# Flight_Controller_SCH.net
KiCad netlist of a schematic drawn in Altium Designer
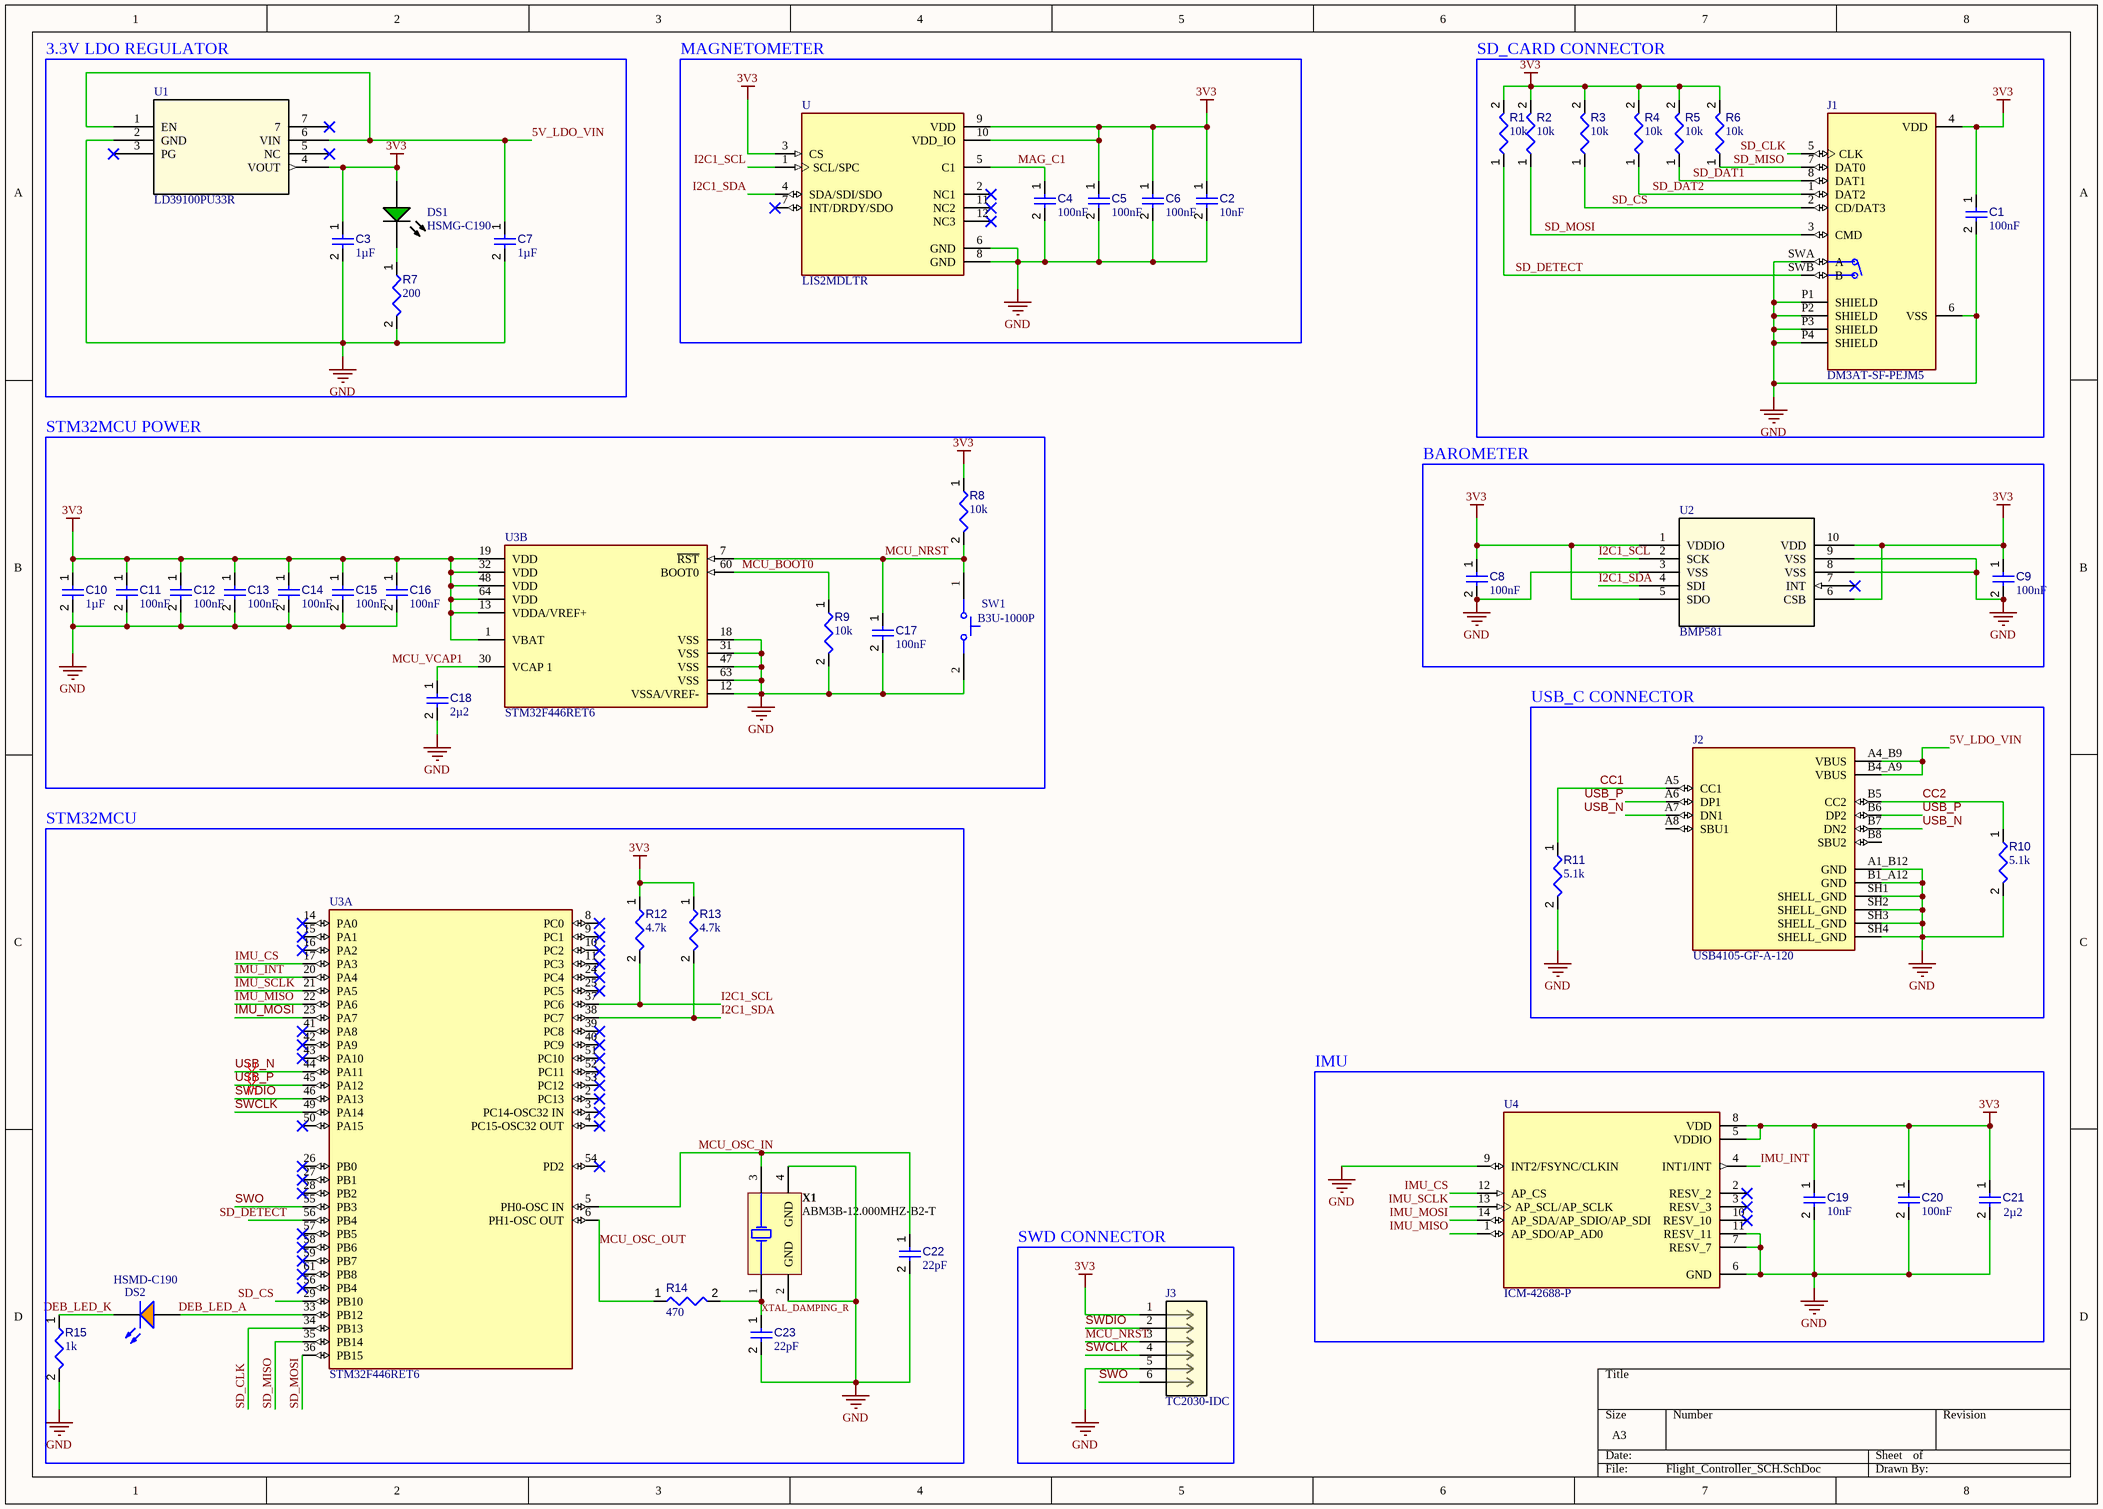
[diagram p0: Flight_Controller_SCH.SchDoc]

(export (version "E")
  (design (tool "Eeschema 10.0.6"))
  (components
    (comp (ref "C1")
      (value "100nF")
      (footprint "CAPC0402(1005)60_L")
      (description "Chip Capacitor, 100nF +/-20%, 25V, 0402, Thickness 0.6 mm")
      (fields (field (name "TOLERANCE") "10%") (field (name "Comment") "Capacitor 100nF +/-20% 25V 0402"))
      (libsource (lib "Jstephe001 Jstephe001") (part "CAP-NP-2"))
    )
    (comp (ref "C2")
      (value "10nF")
      (footprint "CAPC0402(1005)60_L")
      (description "Chip Capacitor, 10nF +/-20%, 50V, 0402, Thickness 0.6 mm")
      (fields (field (name "TOLERANCE") "5%") (field (name "Comment") "Capacitor 10nF +/-20% 50V 0402"))
      (libsource (lib "Jstephe001 Jstephe001") (part "CAP-NP-2"))
    )
    (comp (ref "C3")
      (value "1µF")
      (footprint "CAPC1608X90X35ML15T15")
      (description "Chip Capacitor, 1 uF, +/- 10%, 16 V, 0603 (1608 Metric)")
      (fields (field (name "TOLERANCE") "10%") (field (name "Comment") "Capacitor 1uF +/- 10% 16V 0603"))
      (libsource (lib "Jstephe001 Jstephe001") (part "CAP-NP-2"))
    )
    (comp (ref "C4")
      (value "100nF")
      (footprint "CAPC0402(1005)60_L")
      (description "Chip Capacitor, 100nF +/-20%, 25V, 0402, Thickness 0.6 mm")
      (fields (field (name "TOLERANCE") "10%") (field (name "Comment") "Capacitor 100nF +/-20% 25V 0402"))
      (libsource (lib "Jstephe001 Jstephe001") (part "CAP-NP-2"))
    )
    (comp (ref "C5")
      (value "100nF")
      (footprint "CAPC0402(1005)60_L")
      (description "Chip Capacitor, 100nF +/-20%, 25V, 0402, Thickness 0.6 mm")
      (fields (field (name "TOLERANCE") "10%") (field (name "Comment") "Capacitor 100nF +/-20% 25V 0402"))
      (libsource (lib "Jstephe001 Jstephe001") (part "CAP-NP-2"))
    )
    (comp (ref "C6")
      (value "100nF")
      (footprint "CAPC0402(1005)60_L")
      (description "Chip Capacitor, 100nF +/-20%, 25V, 0402, Thickness 0.6 mm")
      (fields (field (name "TOLERANCE") "10%") (field (name "Comment") "Capacitor 100nF +/-20% 25V 0402"))
      (libsource (lib "Jstephe001 Jstephe001") (part "CAP-NP-2"))
    )
    (comp (ref "C7")
      (value "1µF")
      (footprint "CAPC1608X90X35ML15T15")
      (description "Chip Capacitor, 1 uF, +/- 10%, 16 V, 0603 (1608 Metric)")
      (fields (field (name "TOLERANCE") "10%") (field (name "Comment") "Capacitor 1uF +/- 10% 16V 0603"))
      (libsource (lib "Jstephe001 Jstephe001") (part "CAP-NP-2"))
    )
    (comp (ref "C8")
      (value "100nF")
      (footprint "CAPC0402(1005)60_L")
      (description "Chip Capacitor, 100nF +/-20%, 25V, 0402, Thickness 0.6 mm")
      (fields (field (name "TOLERANCE") "10%") (field (name "Comment") "Capacitor 100nF +/-20% 25V 0402"))
      (libsource (lib "Jstephe001 Jstephe001") (part "CAP-NP-2"))
    )
    (comp (ref "C9")
      (value "100nF")
      (footprint "CAPC0402(1005)60_L")
      (description "Chip Capacitor, 100nF +/-20%, 25V, 0402, Thickness 0.6 mm")
      (fields (field (name "TOLERANCE") "10%") (field (name "Comment") "Capacitor 100nF +/-20% 25V 0402"))
      (libsource (lib "Jstephe001 Jstephe001") (part "CAP-NP-2"))
    )
    (comp (ref "C10")
      (value "1µF")
      (footprint "CAPC1608X90X35ML15T15")
      (description "Chip Capacitor, 1 uF, +/- 10%, 16 V, 0603 (1608 Metric)")
      (fields (field (name "TOLERANCE") "10%") (field (name "Comment") "Capacitor 1uF +/- 10% 16V 0603"))
      (libsource (lib "Jstephe001 Jstephe001") (part "CAP-NP-2"))
    )
    (comp (ref "C11")
      (value "100nF")
      (footprint "CAPC0402(1005)60_L")
      (description "Chip Capacitor, 100nF +/-20%, 25V, 0402, Thickness 0.6 mm")
      (fields (field (name "TOLERANCE") "10%") (field (name "Comment") "Capacitor 100nF +/-20% 25V 0402"))
      (libsource (lib "Jstephe001 Jstephe001") (part "CAP-NP-2"))
    )
    (comp (ref "C12")
      (value "100nF")
      (footprint "CAPC0402(1005)60_L")
      (description "Chip Capacitor, 100nF +/-20%, 25V, 0402, Thickness 0.6 mm")
      (fields (field (name "TOLERANCE") "10%") (field (name "Comment") "Capacitor 100nF +/-20% 25V 0402"))
      (libsource (lib "Jstephe001 Jstephe001") (part "CAP-NP-2"))
    )
    (comp (ref "C13")
      (value "100nF")
      (footprint "CAPC0402(1005)60_L")
      (description "Chip Capacitor, 100nF +/-20%, 25V, 0402, Thickness 0.6 mm")
      (fields (field (name "TOLERANCE") "10%") (field (name "Comment") "Capacitor 100nF +/-20% 25V 0402"))
      (libsource (lib "Jstephe001 Jstephe001") (part "CAP-NP-2"))
    )
    (comp (ref "C14")
      (value "100nF")
      (footprint "CAPC0402(1005)60_L")
      (description "Chip Capacitor, 100nF +/-20%, 25V, 0402, Thickness 0.6 mm")
      (fields (field (name "TOLERANCE") "10%") (field (name "Comment") "Capacitor 100nF +/-20% 25V 0402"))
      (libsource (lib "Jstephe001 Jstephe001") (part "CAP-NP-2"))
    )
    (comp (ref "C15")
      (value "100nF")
      (footprint "CAPC0402(1005)60_L")
      (description "Chip Capacitor, 100nF +/-20%, 25V, 0402, Thickness 0.6 mm")
      (fields (field (name "TOLERANCE") "10%") (field (name "Comment") "Capacitor 100nF +/-20% 25V 0402"))
      (libsource (lib "Jstephe001 Jstephe001") (part "CAP-NP-2"))
    )
    (comp (ref "C16")
      (value "100nF")
      (footprint "CAPC0402(1005)60_L")
      (description "Chip Capacitor, 100nF +/-20%, 25V, 0402, Thickness 0.6 mm")
      (fields (field (name "TOLERANCE") "10%") (field (name "Comment") "Capacitor 100nF +/-20% 25V 0402"))
      (libsource (lib "Jstephe001 Jstephe001") (part "CAP-NP-2"))
    )
    (comp (ref "C17")
      (value "100nF")
      (footprint "CAPC0402(1005)60_L")
      (description "Chip Capacitor, 100nF +/-20%, 25V, 0402, Thickness 0.6 mm")
      (fields (field (name "TOLERANCE") "10%") (field (name "Comment") "Capacitor 100nF +/-20% 25V 0402"))
      (libsource (lib "Jstephe001 Jstephe001") (part "CAP-NP-2"))
    )
    (comp (ref "C18")
      (value "2µ2")
      (footprint "CAPC0402(1005)60_L")
      (description "Chip Capacitor, 2,2µF +/-20%, 10V, 0402, Thickness 0.6 mm")
      (fields (field (name "TOLERANCE") "10%") (field (name "Comment") "Capacitor 2,2µF +/-20% 10V 0402"))
      (libsource (lib "Jstephe001 Jstephe001") (part "CAP-NP-2"))
    )
    (comp (ref "C19")
      (value "10nF")
      (footprint "CAPC0402(1005)60_L")
      (description "Chip Capacitor, 10nF +/-20%, 50V, 0402, Thickness 0.6 mm")
      (fields (field (name "TOLERANCE") "5%") (field (name "Comment") "Capacitor 10nF +/-20% 50V 0402"))
      (libsource (lib "Jstephe001 Jstephe001") (part "CAP-NP-2"))
    )
    (comp (ref "C20")
      (value "100nF")
      (footprint "CAPC1005X56X25LL10T15")
      (description "Chip Capacitor, 0.1 uF, +/- 5%, 16 V, 0402 (1005 Metric)")
      (fields (field (name "TOLERANCE") "5%") (field (name "Comment") "Capacitor 0.1 uF +/- 5% 16 V 0402"))
      (libsource (lib "Jstephe001 Jstephe001") (part "CAP-NP-2"))
    )
    (comp (ref "C21")
      (value "2µ2")
      (footprint "CAPC0402(1005)60_L")
      (description "Chip Capacitor, 2,2µF +/-20%, 10V, 0402, Thickness 0.6 mm")
      (fields (field (name "TOLERANCE") "10%") (field (name "Comment") "Capacitor 2,2µF +/-20% 10V 0402"))
      (libsource (lib "Jstephe001 Jstephe001") (part "CAP-NP-2"))
    )
    (comp (ref "C22")
      (value "22pF")
      (footprint "CAPC0402(1005)60_L")
      (description "Chip Capacitor, 22pF +/-10%, 50V, 0402, Thickness 0.6 mm")
      (fields (field (name "TOLERANCE") "10%") (field (name "Comment") "Capacitor 22pF +/-10% 50V 0402"))
      (libsource (lib "Jstephe001 Jstephe001") (part "CAP-NP-2"))
    )
    (comp (ref "C23")
      (value "22pF")
      (footprint "CAPC0402(1005)60_L")
      (description "Chip Capacitor, 22pF +/-10%, 50V, 0402, Thickness 0.6 mm")
      (fields (field (name "TOLERANCE") "10%") (field (name "Comment") "Capacitor 22pF +/-10% 50V 0402"))
      (libsource (lib "Jstephe001 Jstephe001") (part "CAP-NP-2"))
    )
    (comp (ref "DS1")
      (value "HSMG-C190")
      (footprint "AVAG-HSMX-C190_V")
      (description "LED Uni-Color Green, 52 mW, 20 mA, -40 to 85 degC, 2-Pin SMD, RoHS, Tape and Reel")
      (fields (field (name "POWER") "52mW") (field (name "MANUFACTURER") "Avago"))
      (libsource (lib "Jstephe001 Jstephe001") (part "LED-GREEN-AK-2"))
    )
    (comp (ref "DS2")
      (value "HSMD-C190")
      (footprint "AVAG-HSMX-C190_V")
      (description "LED Uni-Color Orange, 52 mW, 20 mA, -40 to 85 degC, 2-Pin SMD, RoHS, Tape and Reel")
      (fields (field (name "MANUFACTURER") "Avago") (field (name "POWER") "52mW"))
      (libsource (lib "Jstephe001 Jstephe001") (part "LED-ORANGE-AK-2"))
    )
    (comp (ref "J1")
      (value "DM3AT-SF-PEJM5")
      (footprint "HRS_DM3AT-SF-PEJM5")
      (description "10 (8 + 2) Position Card Connector Secure Digital - microSDâ„¢ Surface Mount, Right Angle Gold")
      (fields (field (name "MANUFACTURER") "Hirose Electric Co Ltd"))
      (libsource (lib "Flight_ControllerLib") (part "DM3AT-SF-PEJM5"))
    )
    (comp (ref "J2")
      (value "USB4105-GF-A-120")
      (footprint "GCT_USB4105-GF-A-120")
      (fields (field (name "MF") "Global Connector Technology"))
      (libsource (lib "Jstephe001 Jstephe001") (part "USB4105-GF-A-120"))
    )
    (comp (ref "J3")
      (value "TC2030-IDC")
      (footprint "CONN_TC2030-IDC_TGC")
      (description "Description")
      (libsource (lib "Flight_ControllerLib") (part "TC2030-IDC"))
    )
    (comp (ref "R1")
      (value "10k")
      (footprint "RESC0402(1005)_L")
      (description "Chip Resistor, 10 kOhms, +/-1 %, 63 mW, -55 to 125 degC, 0402")
      (fields (field (name "POWER") "63mW") (field (name "TOLERANCE") "1%"))
      (libsource (lib "Jstephe001 Jstephe001") (part "RES-2"))
    )
    (comp (ref "R2")
      (value "10k")
      (footprint "RESC0402(1005)_L")
      (description "Chip Resistor, 10 kOhms, +/-1 %, 63 mW, -55 to 125 degC, 0402")
      (fields (field (name "POWER") "63mW") (field (name "TOLERANCE") "1%"))
      (libsource (lib "Jstephe001 Jstephe001") (part "RES-2"))
    )
    (comp (ref "R3")
      (value "10k")
      (footprint "RESC0402(1005)_L")
      (description "Chip Resistor, 10 kOhms, +/-1 %, 63 mW, -55 to 125 degC, 0402")
      (fields (field (name "POWER") "63mW") (field (name "TOLERANCE") "1%"))
      (libsource (lib "Jstephe001 Jstephe001") (part "RES-2"))
    )
    (comp (ref "R4")
      (value "10k")
      (footprint "RESC0402(1005)_L")
      (description "Chip Resistor, 10 kOhms, +/-1 %, 63 mW, -55 to 125 degC, 0402")
      (fields (field (name "POWER") "63mW") (field (name "TOLERANCE") "1%"))
      (libsource (lib "Jstephe001 Jstephe001") (part "RES-2"))
    )
    (comp (ref "R5")
      (value "10k")
      (footprint "RESC0402(1005)_L")
      (description "Chip Resistor, 10 kOhms, +/-1 %, 63 mW, -55 to 125 degC, 0402")
      (fields (field (name "POWER") "63mW") (field (name "TOLERANCE") "1%"))
      (libsource (lib "Jstephe001 Jstephe001") (part "RES-2"))
    )
    (comp (ref "R6")
      (value "10k")
      (footprint "RESC0402(1005)_L")
      (description "Chip Resistor, 10 kOhms, +/-1 %, 63 mW, -55 to 125 degC, 0402")
      (fields (field (name "POWER") "63mW") (field (name "TOLERANCE") "1%"))
      (libsource (lib "Jstephe001 Jstephe001") (part "RES-2"))
    )
    (comp (ref "R7")
      (value "200")
      (footprint "RESC0402(1005)_L")
      (description "Chip Resistor, 10 kOhms, +/-1 %, 63 mW, -55 to 125 degC, 0402")
      (fields (field (name "POWER") "63mW") (field (name "TOLERANCE") "1%"))
      (libsource (lib "Jstephe001 Jstephe001") (part "RES-2"))
    )
    (comp (ref "R8")
      (value "10k")
      (footprint "RESC0402(1005)_L")
      (description "Chip Resistor, 10 kOhms, +/-1 %, 63 mW, -55 to 125 degC, 0402")
      (fields (field (name "POWER") "63mW") (field (name "TOLERANCE") "1%"))
      (libsource (lib "Jstephe001 Jstephe001") (part "RES-2"))
    )
    (comp (ref "R9")
      (value "10k")
      (footprint "RESC0402(1005)_L")
      (description "Chip Resistor, 10 kOhms, +/-1 %, 63 mW, -55 to 125 degC, 0402")
      (fields (field (name "POWER") "63mW") (field (name "TOLERANCE") "1%"))
      (libsource (lib "Jstephe001 Jstephe001") (part "RES-2"))
    )
    (comp (ref "R10")
      (value "5.1k")
      (footprint "RESC1005X40N")
      (description "Res Thick Film 0402 5.1K Ohm 1% 0.063W(1/16W) ±100ppm/C Pad SMD T/R")
      (fields (field (name "TOLERANCE") "1%") (field (name "Comment") "0402WGF5101TCE"))
      (libsource (lib "Jstephe001 Jstephe001") (part "RES-2"))
    )
    (comp (ref "R11")
      (value "5.1k")
      (footprint "RESC1005X40N")
      (description "Res Thick Film 0402 5.1K Ohm 1% 0.063W(1/16W) ±100ppm/C Pad SMD T/R")
      (fields (field (name "TOLERANCE") "1%") (field (name "Comment") "0402WGF5101TCE"))
      (libsource (lib "Jstephe001 Jstephe001") (part "RES-2"))
    )
    (comp (ref "R12")
      (value "4.7k")
      (footprint "RESC1005X40X25ML05T05")
      (description "Chip Resistor, 4.7 KOhm, +/- 1%, 0.1 W, -55 to 155 degC, 0402 (1005 Metric)")
      (fields (field (name "POWER") "100mW") (field (name "TOLERANCE") "1%"))
      (libsource (lib "Jstephe001 Jstephe001") (part "RES-2"))
    )
    (comp (ref "R13")
      (value "4.7k")
      (footprint "RESC1005X40X25ML05T05")
      (description "Chip Resistor, 4.7 KOhm, +/- 1%, 0.1 W, -55 to 155 degC, 0402 (1005 Metric)")
      (fields (field (name "POWER") "100mW") (field (name "TOLERANCE") "1%"))
      (libsource (lib "Jstephe001 Jstephe001") (part "RES-2"))
    )
    (comp (ref "R14")
      (value "470")
      (footprint "RESC0805(2012)_L")
      (description "Chip Resistor, 470 Ohms, +/-5%, 125 mW, -55 to 155 degC, 0805")
      (fields (field (name "TOLERANCE") "5%") (field (name "POWER") "125mW"))
      (libsource (lib "Jstephe001 Jstephe001") (part "RES-2"))
    )
    (comp (ref "R15")
      (value "1k")
      (footprint "RESC0402(1005)_L")
      (description "Chip Resistor, 1 kOhms, +/-5 %, 63 mW, -55 to 155 degC, 0402")
      (fields (field (name "TOLERANCE") "5%") (field (name "POWER") "63mW"))
      (libsource (lib "Jstephe001 Jstephe001") (part "RES-2"))
    )
    (comp (ref "SW1")
      (value "B3U-1000P")
      (footprint "OMRON-B3U-1000_V")
      (description "Tactile Switch, SPST-NO, 0.05 A, 12 V, -25 to 70 degC, 2-Pin SMD, RoHS, Tape and Reel")
      (fields (field (name "MANUFACTURER") "Omron Electronic Components"))
      (libsource (lib "Jstephe001 Jstephe001") (part "SW-SPST-NO-2"))
    )
    (comp (ref "U")
      (value "LIS2MDLTR")
      (footprint "LIS2MDLTR")
      (description "Magnetoresistive Sensor X, Y, Z Axis 12-LGA _2x2_")
      (fields (field (name "MANUFACTURER") "STMicroelectronics"))
      (libsource (lib "Flight_ControllerLib") (part "LIS2MDLTR"))
    )
    (comp (ref "U1")
      (value "LD39100PU33R")
      (footprint "DFN_00PU33R_STM")
      (description "1 A low quiescent current low noise voltage regulator")
      (libsource (lib "Flight_ControllerLib") (part "LD39100PU33R"))
    )
    (comp (ref "U2")
      (value "BMP581")
      (footprint "QFN10_BMP581_BOS-M")
      (description "No Description Available")
      (fields (field (name "COPYRIGHT") "Copyright (C) 2026 Ultra Librarian. All rights reserved."))
      (libsource (lib "Flight_ControllerLib") (part "BMP581"))
    )
    (comp (ref "U3")
      (value "STM32F446RET6")
      (footprint "FP-LQFP64-5W-MFG")
      (description "IC MCU 32BIT 512KB FLASH 64LQFP")
      (fields
        (field (name "OCTOPART") "https://octopart.com/stm32f446ret6-stmicroelectronics-52642920")
        (field (name "MANUFACTURER") "ST")
      )
      (libsource (lib "") (part "ee11adc32c0ab33b933cccf4348c338_1"))
    )
    (comp (ref "U4")
      (value "ICM-42688-P")
      (footprint "Flight_ControllerPCBlib:ICM-42688-P")
      (description "Accelerometer, Gyroscope, 6 Axis Sensor Output")
      (libsource (lib "Flight_ControllerLib") (part "ICM-42688-P"))
    )
    (comp (ref "X1")
      (value "ABM3B-12.000MHZ-B2-T")
      (footprint "ABRA-ABM3B-4_V")
      (description "Ceramic SMD Crystal, 12 MHz, +/- 20 ppm, 18 pF, -20 to 70 degC, 4-Pin SMD, RoHS, Tape and Reel")
      (fields (field (name "TOLERANCE") "20ppm") (field (name "MANUFACTURER") "Abracon"))
      (libsource (lib "Jstephe001 Jstephe001") (part "XTAL-1-3-4"))
    )
  )
  (nets
    (net (code "1") (name "/5V_LDO_VIN") (class "Default")
      (node (ref "C7") (pin "1") (pinfunction "1_1") (pintype "passive"))
      (node (ref "J2") (pin "A4_B9") (pinfunction "VBUS_A4_B9") (pintype "power_in"))
      (node (ref "J2") (pin "B4_A9") (pinfunction "VBUS_B4_A9") (pintype "power_in"))
      (node (ref "U1") (pin "1") (pinfunction "EN_1") (pintype "passive"))
      (node (ref "U1") (pin "6") (pinfunction "VIN_6") (pintype "passive"))
    )
    (net (code "2") (name "/CC1") (class "Default")
      (node (ref "J2") (pin "A5") (pinfunction "CC1_A5") (pintype "bidirectional"))
      (node (ref "R11") (pin "1") (pinfunction "1_1") (pintype "passive"))
    )
    (net (code "3") (name "/CC2") (class "Default")
      (node (ref "J2") (pin "B5") (pinfunction "CC2_B5") (pintype "bidirectional"))
      (node (ref "R10") (pin "1") (pinfunction "1_1") (pintype "passive"))
    )
    (net (code "4") (name "/DEB_LED_A") (class "Default")
      (node (ref "DS2") (pin "1") (pinfunction "A_1") (pintype "passive"))
      (node (ref "U3") (pin "33") (pinfunction "PB12_33") (pintype "bidirectional"))
    )
    (net (code "5") (name "/DEB_LED_K") (class "Default")
      (node (ref "DS2") (pin "2") (pinfunction "K_2") (pintype "passive"))
      (node (ref "R15") (pin "1") (pinfunction "1_1") (pintype "passive"))
    )
    (net (code "6") (name "/I2C1_SCL") (class "Default")
      (node (ref "R12") (pin "2") (pinfunction "2_2") (pintype "passive"))
      (node (ref "U") (pin "1") (pinfunction "SCL/SPC_1") (pintype "input"))
      (node (ref "U2") (pin "2") (pinfunction "SCK_2") (pintype "passive"))
      (node (ref "U3") (pin "37") (pinfunction "PC6_37") (pintype "bidirectional"))
    )
    (net (code "7") (name "/I2C1_SDA") (class "Default")
      (node (ref "R13") (pin "2") (pinfunction "2_2") (pintype "passive"))
      (node (ref "U") (pin "4") (pinfunction "SDA/SDI/SDO_4") (pintype "bidirectional"))
      (node (ref "U2") (pin "4") (pinfunction "SDI_4") (pintype "passive"))
      (node (ref "U3") (pin "38") (pinfunction "PC7_38") (pintype "bidirectional"))
    )
    (net (code "8") (name "/IMU_CS") (class "Default")
      (node (ref "U3") (pin "17") (pinfunction "PA3_17") (pintype "bidirectional"))
      (node (ref "U4") (pin "12") (pinfunction "AP_CS_12") (pintype "input"))
    )
    (net (code "9") (name "/IMU_INT") (class "Default")
      (node (ref "U3") (pin "20") (pinfunction "PA4_20") (pintype "bidirectional"))
      (node (ref "U4") (pin "4") (pinfunction "INT1/INT_4") (pintype "output"))
    )
    (net (code "10") (name "/IMU_MISO") (class "Default")
      (node (ref "U3") (pin "22") (pinfunction "PA6_22") (pintype "bidirectional"))
      (node (ref "U4") (pin "1") (pinfunction "AP_SDO/AP_AD0_1") (pintype "bidirectional"))
    )
    (net (code "11") (name "/IMU_MOSI") (class "Default")
      (node (ref "U3") (pin "23") (pinfunction "PA7_23") (pintype "bidirectional"))
      (node (ref "U4") (pin "14") (pinfunction "AP_SDA/AP_SDIO/AP_SDI_14") (pintype "bidirectional"))
    )
    (net (code "12") (name "/IMU_SCLK") (class "Default")
      (node (ref "U3") (pin "21") (pinfunction "PA5_21") (pintype "bidirectional"))
      (node (ref "U4") (pin "13") (pinfunction "AP_SCL/AP_SCLK_13") (pintype "input"))
    )
    (net (code "13") (name "/MAG_C1") (class "Default")
      (node (ref "C4") (pin "1") (pinfunction "1_1") (pintype "passive"))
      (node (ref "U") (pin "5") (pinfunction "C1_5") (pintype "passive"))
    )
    (net (code "14") (name "/MCU_BOOT0") (class "Default")
      (node (ref "R9") (pin "1") (pinfunction "1_1") (pintype "passive"))
      (node (ref "U3") (pin "60") (pinfunction "BOOT0_60") (pintype "input"))
    )
    (net (code "15") (name "/MCU_NRST") (class "Default")
      (node (ref "C17") (pin "1") (pinfunction "1_1") (pintype "passive"))
      (node (ref "J3") (pin "3") (pinfunction "3_3") (pintype "passive"))
      (node (ref "R8") (pin "2") (pinfunction "2_2") (pintype "passive"))
      (node (ref "SW1") (pin "1") (pinfunction "1_1") (pintype "passive"))
      (node (ref "U3") (pin "7") (pinfunction "~{RST}_7") (pintype "input"))
    )
    (net (code "16") (name "/MCU_OSC_IN") (class "Default")
      (node (ref "C22") (pin "1") (pinfunction "1_1") (pintype "passive"))
      (node (ref "U3") (pin "5") (pinfunction "PH0-OSC_IN_5") (pintype "bidirectional"))
      (node (ref "X1") (pin "3") (pinfunction "X2_3") (pintype "passive"))
    )
    (net (code "17") (name "/MCU_OSC_OUT") (class "Default")
      (node (ref "R14") (pin "1") (pinfunction "1_1") (pintype "passive"))
      (node (ref "U3") (pin "6") (pinfunction "PH1-OSC_OUT_6") (pintype "bidirectional"))
    )
    (net (code "18") (name "/MCU_VCAP1") (class "Default")
      (node (ref "C18") (pin "1") (pinfunction "1_1") (pintype "passive"))
      (node (ref "U3") (pin "30") (pinfunction "VCAP_1_30") (pintype "power_in"))
    )
    (net (code "19") (name "/SD_CLK") (class "Default")
      (node (ref "J1") (pin "5") (pinfunction "CLK_5") (pintype "bidirectional"))
      (node (ref "U3") (pin "34") (pinfunction "PB13_34") (pintype "bidirectional"))
    )
    (net (code "20") (name "/SD_CS") (class "Default")
      (node (ref "J1") (pin "2") (pinfunction "CD/DAT3_2") (pintype "bidirectional"))
      (node (ref "R3") (pin "1") (pinfunction "1_1") (pintype "passive"))
      (node (ref "U3") (pin "29") (pinfunction "PB10_29") (pintype "bidirectional"))
    )
    (net (code "21") (name "/SD_DAT1") (class "Default")
      (node (ref "J1") (pin "8") (pinfunction "DAT1_8") (pintype "bidirectional"))
      (node (ref "R5") (pin "1") (pinfunction "1_1") (pintype "passive"))
    )
    (net (code "22") (name "/SD_DAT2") (class "Default")
      (node (ref "J1") (pin "1") (pinfunction "DAT2_1") (pintype "bidirectional"))
      (node (ref "R4") (pin "1") (pinfunction "1_1") (pintype "passive"))
    )
    (net (code "23") (name "/SD_DETECT") (class "Default")
      (node (ref "J1") (pin "SWB") (pinfunction "B_SWB") (pintype "bidirectional"))
      (node (ref "R1") (pin "1") (pinfunction "1_1") (pintype "passive"))
      (node (ref "U3") (pin "56") (pinfunction "PB4_56") (pintype "bidirectional"))
    )
    (net (code "24") (name "/SD_MISO") (class "Default")
      (node (ref "J1") (pin "7") (pinfunction "DAT0_7") (pintype "bidirectional"))
      (node (ref "R6") (pin "1") (pinfunction "1_1") (pintype "passive"))
      (node (ref "U3") (pin "35") (pinfunction "PB14_35") (pintype "bidirectional"))
    )
    (net (code "25") (name "/SD_MOSI") (class "Default")
      (node (ref "J1") (pin "3") (pinfunction "CMD_3") (pintype "bidirectional"))
      (node (ref "R2") (pin "1") (pinfunction "1_1") (pintype "passive"))
      (node (ref "U3") (pin "36") (pinfunction "PB15_36") (pintype "bidirectional"))
    )
    (net (code "26") (name "/SWCLK") (class "Default")
      (node (ref "J3") (pin "4") (pinfunction "4_4") (pintype "passive"))
      (node (ref "U3") (pin "49") (pinfunction "PA14_49") (pintype "bidirectional"))
    )
    (net (code "27") (name "/SWDIO") (class "Default")
      (node (ref "J3") (pin "2") (pinfunction "2_2") (pintype "passive"))
      (node (ref "U3") (pin "46") (pinfunction "PA13_46") (pintype "bidirectional"))
    )
    (net (code "28") (name "/SWO") (class "Default")
      (node (ref "J3") (pin "6") (pinfunction "6_6") (pintype "passive"))
      (node (ref "U3") (pin "55") (pinfunction "PB3_55") (pintype "bidirectional"))
    )
    (net (code "29") (name "/USB_N") (class "Default")
      (node (ref "J2") (pin "A7") (pinfunction "DN1_A7") (pintype "bidirectional"))
      (node (ref "J2") (pin "B7") (pinfunction "DN2_B7") (pintype "bidirectional"))
      (node (ref "U3") (pin "44") (pinfunction "PA11_44") (pintype "bidirectional"))
    )
    (net (code "30") (name "/USB_P") (class "Default")
      (node (ref "J2") (pin "A6") (pinfunction "DP1_A6") (pintype "bidirectional"))
      (node (ref "J2") (pin "B6") (pinfunction "DP2_B6") (pintype "bidirectional"))
      (node (ref "U3") (pin "45") (pinfunction "PA12_45") (pintype "bidirectional"))
    )
    (net (code "31") (name "/XTAL_DAMPING_R") (class "Default")
      (node (ref "C23") (pin "1") (pinfunction "1_1") (pintype "passive"))
      (node (ref "R14") (pin "2") (pinfunction "2_2") (pintype "passive"))
      (node (ref "X1") (pin "1") (pinfunction "X1_1") (pintype "passive"))
    )
    (net (code "32") (name "3V3") (class "Default")
      (node (ref "C1") (pin "1") (pinfunction "1_1") (pintype "passive"))
      (node (ref "C10") (pin "1") (pinfunction "1_1") (pintype "passive"))
      (node (ref "C11") (pin "1") (pinfunction "1_1") (pintype "passive"))
      (node (ref "C12") (pin "1") (pinfunction "1_1") (pintype "passive"))
      (node (ref "C13") (pin "1") (pinfunction "1_1") (pintype "passive"))
      (node (ref "C14") (pin "1") (pinfunction "1_1") (pintype "passive"))
      (node (ref "C15") (pin "1") (pinfunction "1_1") (pintype "passive"))
      (node (ref "C16") (pin "1") (pinfunction "1_1") (pintype "passive"))
      (node (ref "C19") (pin "1") (pinfunction "1_1") (pintype "passive"))
      (node (ref "C2") (pin "1") (pinfunction "1_1") (pintype "passive"))
      (node (ref "C20") (pin "1") (pinfunction "1_1") (pintype "passive"))
      (node (ref "C21") (pin "1") (pinfunction "1_1") (pintype "passive"))
      (node (ref "C3") (pin "1") (pinfunction "1_1") (pintype "passive"))
      (node (ref "C5") (pin "1") (pinfunction "1_1") (pintype "passive"))
      (node (ref "C6") (pin "1") (pinfunction "1_1") (pintype "passive"))
      (node (ref "C8") (pin "1") (pinfunction "1_1") (pintype "passive"))
      (node (ref "C9") (pin "1") (pinfunction "1_1") (pintype "passive"))
      (node (ref "DS1") (pin "1") (pinfunction "A_1") (pintype "passive"))
      (node (ref "J1") (pin "4") (pinfunction "VDD_4") (pintype "power_in"))
      (node (ref "J3") (pin "1") (pinfunction "1_1") (pintype "passive"))
      (node (ref "R1") (pin "2") (pinfunction "2_2") (pintype "passive"))
      (node (ref "R12") (pin "1") (pinfunction "1_1") (pintype "passive"))
      (node (ref "R13") (pin "1") (pinfunction "1_1") (pintype "passive"))
      (node (ref "R2") (pin "2") (pinfunction "2_2") (pintype "passive"))
      (node (ref "R3") (pin "2") (pinfunction "2_2") (pintype "passive"))
      (node (ref "R4") (pin "2") (pinfunction "2_2") (pintype "passive"))
      (node (ref "R5") (pin "2") (pinfunction "2_2") (pintype "passive"))
      (node (ref "R6") (pin "2") (pinfunction "2_2") (pintype "passive"))
      (node (ref "R8") (pin "1") (pinfunction "1_1") (pintype "passive"))
      (node (ref "U") (pin "10") (pinfunction "VDD_IO_10") (pintype "power_in"))
      (node (ref "U") (pin "3") (pinfunction "CS_3") (pintype "input"))
      (node (ref "U") (pin "9") (pinfunction "VDD_9") (pintype "power_in"))
      (node (ref "U1") (pin "4") (pinfunction "VOUT_4") (pintype "output"))
      (node (ref "U2") (pin "1") (pinfunction "VDDIO_1") (pintype "power_in"))
      (node (ref "U2") (pin "10") (pinfunction "VDD_10") (pintype "power_in"))
      (node (ref "U2") (pin "5") (pinfunction "SDO_5") (pintype "passive"))
      (node (ref "U2") (pin "6") (pinfunction "CSB_6") (pintype "passive"))
      (node (ref "U3") (pin "1") (pinfunction "VBAT_1") (pintype "power_in"))
      (node (ref "U3") (pin "13") (pinfunction "VDDA/VREF+_13") (pintype "power_in"))
      (node (ref "U3") (pin "19") (pinfunction "VDD_19") (pintype "power_in"))
      (node (ref "U3") (pin "32") (pinfunction "VDD_32") (pintype "power_in"))
      (node (ref "U3") (pin "48") (pinfunction "VDD_48") (pintype "power_in"))
      (node (ref "U3") (pin "64") (pinfunction "VDD_64") (pintype "power_in"))
      (node (ref "U4") (pin "5") (pinfunction "VDDIO_5") (pintype "power_in"))
      (node (ref "U4") (pin "8") (pinfunction "VDD_8") (pintype "power_in"))
    )
    (net (code "33") (name "GND") (class "Default")
      (node (ref "C1") (pin "2") (pinfunction "2_2") (pintype "passive"))
      (node (ref "C10") (pin "2") (pinfunction "2_2") (pintype "passive"))
      (node (ref "C11") (pin "2") (pinfunction "2_2") (pintype "passive"))
      (node (ref "C12") (pin "2") (pinfunction "2_2") (pintype "passive"))
      (node (ref "C13") (pin "2") (pinfunction "2_2") (pintype "passive"))
      (node (ref "C14") (pin "2") (pinfunction "2_2") (pintype "passive"))
      (node (ref "C15") (pin "2") (pinfunction "2_2") (pintype "passive"))
      (node (ref "C16") (pin "2") (pinfunction "2_2") (pintype "passive"))
      (node (ref "C17") (pin "2") (pinfunction "2_2") (pintype "passive"))
      (node (ref "C18") (pin "2") (pinfunction "2_2") (pintype "passive"))
      (node (ref "C19") (pin "2") (pinfunction "2_2") (pintype "passive"))
      (node (ref "C2") (pin "2") (pinfunction "2_2") (pintype "passive"))
      (node (ref "C20") (pin "2") (pinfunction "2_2") (pintype "passive"))
      (node (ref "C21") (pin "2") (pinfunction "2_2") (pintype "passive"))
      (node (ref "C22") (pin "2") (pinfunction "2_2") (pintype "passive"))
      (node (ref "C23") (pin "2") (pinfunction "2_2") (pintype "passive"))
      (node (ref "C3") (pin "2") (pinfunction "2_2") (pintype "passive"))
      (node (ref "C4") (pin "2") (pinfunction "2_2") (pintype "passive"))
      (node (ref "C5") (pin "2") (pinfunction "2_2") (pintype "passive"))
      (node (ref "C6") (pin "2") (pinfunction "2_2") (pintype "passive"))
      (node (ref "C7") (pin "2") (pinfunction "2_2") (pintype "passive"))
      (node (ref "C8") (pin "2") (pinfunction "2_2") (pintype "passive"))
      (node (ref "C9") (pin "2") (pinfunction "2_2") (pintype "passive"))
      (node (ref "J1") (pin "6") (pinfunction "VSS_6") (pintype "power_in"))
      (node (ref "J1") (pin "P1") (pinfunction "SHIELD_P1") (pintype "passive"))
      (node (ref "J1") (pin "P2") (pinfunction "SHIELD_P2") (pintype "passive"))
      (node (ref "J1") (pin "P3") (pinfunction "SHIELD_P3") (pintype "passive"))
      (node (ref "J1") (pin "P4") (pinfunction "SHIELD_P4") (pintype "passive"))
      (node (ref "J1") (pin "SWA") (pinfunction "A_SWA") (pintype "bidirectional"))
      (node (ref "J2") (pin "A1_B12") (pinfunction "GND_A1_B12") (pintype "power_in"))
      (node (ref "J2") (pin "B1_A12") (pinfunction "GND_B1_A12") (pintype "power_in"))
      (node (ref "J2") (pin "SH1") (pinfunction "SHELL_GND_SH1") (pintype "power_in"))
      (node (ref "J2") (pin "SH2") (pinfunction "SHELL_GND_SH2") (pintype "power_in"))
      (node (ref "J2") (pin "SH3") (pinfunction "SHELL_GND_SH3") (pintype "power_in"))
      (node (ref "J2") (pin "SH4") (pinfunction "SHELL_GND_SH4") (pintype "power_in"))
      (node (ref "J3") (pin "5") (pinfunction "5_5") (pintype "passive"))
      (node (ref "R10") (pin "2") (pinfunction "2_2") (pintype "passive"))
      (node (ref "R11") (pin "2") (pinfunction "2_2") (pintype "passive"))
      (node (ref "R15") (pin "2") (pinfunction "2_2") (pintype "passive"))
      (node (ref "R7") (pin "2") (pinfunction "2_2") (pintype "passive"))
      (node (ref "R9") (pin "2") (pinfunction "2_2") (pintype "passive"))
      (node (ref "SW1") (pin "2") (pinfunction "2_2") (pintype "passive"))
      (node (ref "U") (pin "6") (pinfunction "GND_6") (pintype "power_in"))
      (node (ref "U") (pin "8") (pinfunction "GND_8") (pintype "power_in"))
      (node (ref "U1") (pin "2") (pinfunction "GND_2") (pintype "power_in"))
      (node (ref "U2") (pin "3") (pinfunction "VSS_3") (pintype "power_in"))
      (node (ref "U2") (pin "8") (pinfunction "VSS_8") (pintype "power_in"))
      (node (ref "U2") (pin "9") (pinfunction "VSS_9") (pintype "power_in"))
      (node (ref "U3") (pin "12") (pinfunction "VSSA/VREF-_12") (pintype "power_in"))
      (node (ref "U3") (pin "18") (pinfunction "VSS_18") (pintype "power_in"))
      (node (ref "U3") (pin "31") (pinfunction "VSS_31") (pintype "power_in"))
      (node (ref "U3") (pin "47") (pinfunction "VSS_47") (pintype "power_in"))
      (node (ref "U3") (pin "63") (pinfunction "VSS_63") (pintype "power_in"))
      (node (ref "U4") (pin "11") (pinfunction "RESV_11_11") (pintype "passive"))
      (node (ref "U4") (pin "6") (pinfunction "GND_6") (pintype "power_in"))
      (node (ref "U4") (pin "7") (pinfunction "RESV_7_7") (pintype "passive"))
      (node (ref "U4") (pin "9") (pinfunction "INT2/FSYNC/CLKIN_9") (pintype "bidirectional"))
      (node (ref "X1") (pin "2") (pinfunction "GND_2") (pintype "power_in"))
      (node (ref "X1") (pin "4") (pinfunction "GND_4") (pintype "power_in"))
    )
    (net (code "34") (name "Net-(DS1-K)") (class "Default")
      (node (ref "DS1") (pin "2") (pinfunction "K_2") (pintype "passive"))
      (node (ref "R7") (pin "1") (pinfunction "1_1") (pintype "passive"))
    )
    (net (code "35") (name "unconnected-(J2-SBU1-PadA8)") (class "Default")
      (node (ref "J2") (pin "A8") (pinfunction "SBU1_A8") (pintype "bidirectional"))
    )
    (net (code "36") (name "unconnected-(J2-SBU2-PadB8)") (class "Default")
      (node (ref "J2") (pin "B8") (pinfunction "SBU2_B8") (pintype "bidirectional"))
    )
    (net (code "37") (name "unconnected-(U-INT{slash}DRDY{slash}SDO-Pad7)") (class "Default")
      (node (ref "U") (pin "7") (pinfunction "INT/DRDY/SDO_7") (pintype "bidirectional+no_connect"))
    )
    (net (code "38") (name "unconnected-(U-NC1-Pad2)") (class "Default")
      (node (ref "U") (pin "2") (pinfunction "NC1_2") (pintype "passive+no_connect"))
    )
    (net (code "39") (name "unconnected-(U-NC2-Pad11)") (class "Default")
      (node (ref "U") (pin "11") (pinfunction "NC2_11") (pintype "passive+no_connect"))
    )
    (net (code "40") (name "unconnected-(U-NC3-Pad12)") (class "Default")
      (node (ref "U") (pin "12") (pinfunction "NC3_12") (pintype "passive+no_connect"))
    )
    (net (code "41") (name "unconnected-(U1-NC-Pad5)") (class "Default")
      (node (ref "U1") (pin "5") (pinfunction "NC_5") (pintype "passive+no_connect"))
    )
    (net (code "42") (name "unconnected-(U1-PG-Pad3)") (class "Default")
      (node (ref "U1") (pin "3") (pinfunction "PG_3") (pintype "passive+no_connect"))
    )
    (net (code "43") (name "unconnected-(U1-Pad7)") (class "Default")
      (node (ref "U1") (pin "7") (pinfunction "7_7") (pintype "passive+no_connect"))
    )
    (net (code "44") (name "unconnected-(U2-INT-Pad7)") (class "Default")
      (node (ref "U2") (pin "7") (pinfunction "INT_7") (pintype "input+no_connect"))
    )
    (net (code "45") (name "unconnected-(U3A-PA0-Pad14)") (class "Default")
      (node (ref "U3") (pin "14") (pinfunction "PA0_14") (pintype "bidirectional+no_connect"))
    )
    (net (code "46") (name "unconnected-(U3A-PA1-Pad15)") (class "Default")
      (node (ref "U3") (pin "15") (pinfunction "PA1_15") (pintype "bidirectional+no_connect"))
    )
    (net (code "47") (name "unconnected-(U3A-PA2-Pad16)") (class "Default")
      (node (ref "U3") (pin "16") (pinfunction "PA2_16") (pintype "bidirectional+no_connect"))
    )
    (net (code "48") (name "unconnected-(U3A-PA8-Pad41)") (class "Default")
      (node (ref "U3") (pin "41") (pinfunction "PA8_41") (pintype "bidirectional+no_connect"))
    )
    (net (code "49") (name "unconnected-(U3A-PA9-Pad42)") (class "Default")
      (node (ref "U3") (pin "42") (pinfunction "PA9_42") (pintype "bidirectional+no_connect"))
    )
    (net (code "50") (name "unconnected-(U3A-PA10-Pad43)") (class "Default")
      (node (ref "U3") (pin "43") (pinfunction "PA10_43") (pintype "bidirectional+no_connect"))
    )
    (net (code "51") (name "unconnected-(U3A-PA15-Pad50)") (class "Default")
      (node (ref "U3") (pin "50") (pinfunction "PA15_50") (pintype "bidirectional+no_connect"))
    )
    (net (code "52") (name "unconnected-(U3A-PB0-Pad26)") (class "Default")
      (node (ref "U3") (pin "26") (pinfunction "PB0_26") (pintype "bidirectional+no_connect"))
    )
    (net (code "53") (name "unconnected-(U3A-PB1-Pad27)") (class "Default")
      (node (ref "U3") (pin "27") (pinfunction "PB1_27") (pintype "bidirectional+no_connect"))
    )
    (net (code "54") (name "unconnected-(U3A-PB2-Pad28)") (class "Default")
      (node (ref "U3") (pin "28") (pinfunction "PB2_28") (pintype "bidirectional+no_connect"))
    )
    (net (code "55") (name "unconnected-(U3A-PB4-Pad56)") (class "Default")
      (node (ref "U3") (pin "56") (pinfunction "PB4_56") (pintype "bidirectional+no_connect"))
    )
    (net (code "56") (name "unconnected-(U3A-PB5-Pad57)") (class "Default")
      (node (ref "U3") (pin "57") (pinfunction "PB5_57") (pintype "bidirectional+no_connect"))
    )
    (net (code "57") (name "unconnected-(U3A-PB6-Pad58)") (class "Default")
      (node (ref "U3") (pin "58") (pinfunction "PB6_58") (pintype "bidirectional+no_connect"))
    )
    (net (code "58") (name "unconnected-(U3A-PB7-Pad59)") (class "Default")
      (node (ref "U3") (pin "59") (pinfunction "PB7_59") (pintype "bidirectional+no_connect"))
    )
    (net (code "59") (name "unconnected-(U3A-PB8-Pad61)") (class "Default")
      (node (ref "U3") (pin "61") (pinfunction "PB8_61") (pintype "bidirectional+no_connect"))
    )
    (net (code "60") (name "unconnected-(U3A-PC0-Pad8)") (class "Default")
      (node (ref "U3") (pin "8") (pinfunction "PC0_8") (pintype "bidirectional+no_connect"))
    )
    (net (code "61") (name "unconnected-(U3A-PC1-Pad9)") (class "Default")
      (node (ref "U3") (pin "9") (pinfunction "PC1_9") (pintype "bidirectional+no_connect"))
    )
    (net (code "62") (name "unconnected-(U3A-PC2-Pad10)") (class "Default")
      (node (ref "U3") (pin "10") (pinfunction "PC2_10") (pintype "bidirectional+no_connect"))
    )
    (net (code "63") (name "unconnected-(U3A-PC3-Pad11)") (class "Default")
      (node (ref "U3") (pin "11") (pinfunction "PC3_11") (pintype "bidirectional+no_connect"))
    )
    (net (code "64") (name "unconnected-(U3A-PC4-Pad24)") (class "Default")
      (node (ref "U3") (pin "24") (pinfunction "PC4_24") (pintype "bidirectional+no_connect"))
    )
    (net (code "65") (name "unconnected-(U3A-PC5-Pad25)") (class "Default")
      (node (ref "U3") (pin "25") (pinfunction "PC5_25") (pintype "bidirectional+no_connect"))
    )
    (net (code "66") (name "unconnected-(U3A-PC8-Pad39)") (class "Default")
      (node (ref "U3") (pin "39") (pinfunction "PC8_39") (pintype "bidirectional+no_connect"))
    )
    (net (code "67") (name "unconnected-(U3A-PC9-Pad40)") (class "Default")
      (node (ref "U3") (pin "40") (pinfunction "PC9_40") (pintype "bidirectional+no_connect"))
    )
    (net (code "68") (name "unconnected-(U3A-PC10-Pad51)") (class "Default")
      (node (ref "U3") (pin "51") (pinfunction "PC10_51") (pintype "bidirectional+no_connect"))
    )
    (net (code "69") (name "unconnected-(U3A-PC11-Pad52)") (class "Default")
      (node (ref "U3") (pin "52") (pinfunction "PC11_52") (pintype "bidirectional+no_connect"))
    )
    (net (code "70") (name "unconnected-(U3A-PC12-Pad53)") (class "Default")
      (node (ref "U3") (pin "53") (pinfunction "PC12_53") (pintype "bidirectional+no_connect"))
    )
    (net (code "71") (name "unconnected-(U3A-PC13-Pad2)") (class "Default")
      (node (ref "U3") (pin "2") (pinfunction "PC13_2") (pintype "bidirectional+no_connect"))
    )
    (net (code "72") (name "unconnected-(U3A-PC14-OSC32_IN-Pad3)") (class "Default")
      (node (ref "U3") (pin "3") (pinfunction "PC14-OSC32_IN_3") (pintype "bidirectional+no_connect"))
    )
    (net (code "73") (name "unconnected-(U3A-PC15-OSC32_OUT-Pad4)") (class "Default")
      (node (ref "U3") (pin "4") (pinfunction "PC15-OSC32_OUT_4") (pintype "bidirectional+no_connect"))
    )
    (net (code "74") (name "unconnected-(U3A-PD2-Pad54)") (class "Default")
      (node (ref "U3") (pin "54") (pinfunction "PD2_54") (pintype "bidirectional+no_connect"))
    )
    (net (code "75") (name "unconnected-(U4-RESV_2-Pad2)") (class "Default")
      (node (ref "U4") (pin "2") (pinfunction "RESV_2_2") (pintype "passive+no_connect"))
    )
    (net (code "76") (name "unconnected-(U4-RESV_3-Pad3)") (class "Default")
      (node (ref "U4") (pin "3") (pinfunction "RESV_3_3") (pintype "passive+no_connect"))
    )
    (net (code "77") (name "unconnected-(U4-RESV_10-Pad10)") (class "Default")
      (node (ref "U4") (pin "10") (pinfunction "RESV_10_10") (pintype "passive+no_connect"))
    )
  )
)
